# FPGA.net
KiCad netlist of a schematic drawn in Altium Designer
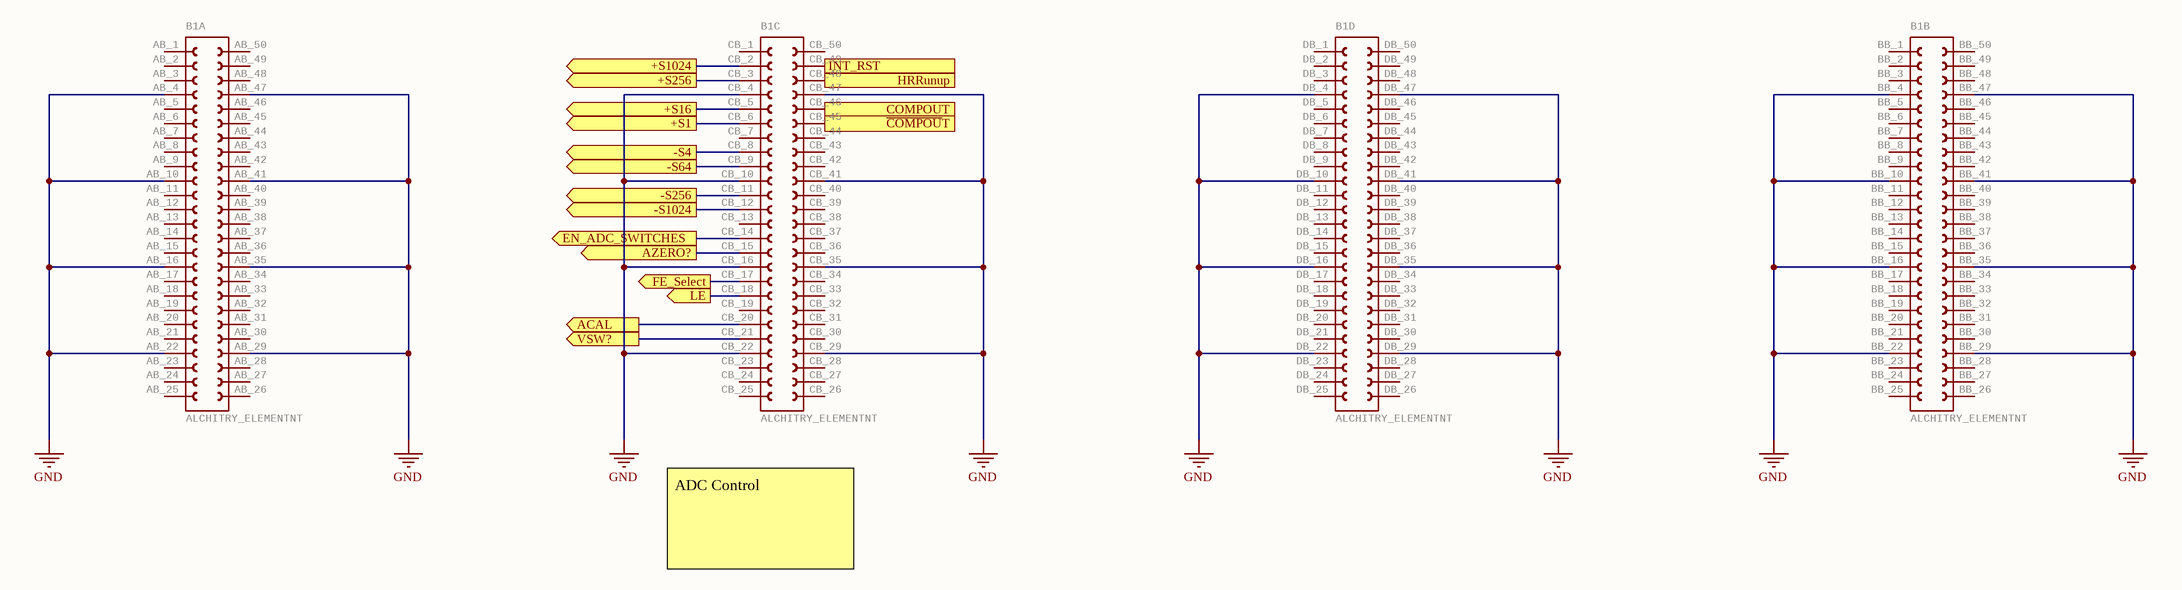
[diagram p0: FPGA.SchDoc]

(export (version "E")
  (design (tool "Eeschema 10.0.6"))
  (components
    (comp (ref "B1")
      (value "ALCHITRY_ELEMENTNT")
      (footprint "ELEMENT_NO_TOP")
      (libsource (lib "alchitry_elements.Library") (part "ALCHITRY_ELEMENTNT"))
    )
  )
  (nets
    (net (code "1") (name "/+S1") (class "Default")
      (node (ref "B1") (pin "CB_6") (pinfunction "6_CB_6") (pintype "passive"))
    )
    (net (code "2") (name "/+S16") (class "Default")
      (node (ref "B1") (pin "CB_5") (pinfunction "5_CB_5") (pintype "passive"))
    )
    (net (code "3") (name "/+S256") (class "Default")
      (node (ref "B1") (pin "CB_3") (pinfunction "3_CB_3") (pintype "passive"))
    )
    (net (code "4") (name "/+S1024") (class "Default")
      (node (ref "B1") (pin "CB_2") (pinfunction "2_CB_2") (pintype "passive"))
    )
    (net (code "5") (name "/-S4") (class "Default")
      (node (ref "B1") (pin "CB_8") (pinfunction "8_CB_8") (pintype "passive"))
    )
    (net (code "6") (name "/-S64") (class "Default")
      (node (ref "B1") (pin "CB_9") (pinfunction "9_CB_9") (pintype "passive"))
    )
    (net (code "7") (name "/-S256") (class "Default")
      (node (ref "B1") (pin "CB_11") (pinfunction "11_CB_11") (pintype "passive"))
    )
    (net (code "8") (name "/-S1024") (class "Default")
      (node (ref "B1") (pin "CB_12") (pinfunction "12_CB_12") (pintype "passive"))
    )
    (net (code "9") (name "/ACAL") (class "Default")
      (node (ref "B1") (pin "CB_20") (pinfunction "20_CB_20") (pintype "passive"))
    )
    (net (code "10") (name "/AZERO?") (class "Default")
      (node (ref "B1") (pin "CB_15") (pinfunction "15_CB_15") (pintype "passive"))
    )
    (net (code "11") (name "/COMPOUT") (class "Default")
      (node (ref "B1") (pin "CB_46") (pinfunction "46_CB_46") (pintype "passive"))
    )
    (net (code "12") (name "/EN_ADC_SWITCHES") (class "Default")
      (node (ref "B1") (pin "CB_14") (pinfunction "14_CB_14") (pintype "passive"))
    )
    (net (code "13") (name "/FE_Select") (class "Default")
      (node (ref "B1") (pin "CB_17") (pinfunction "17_CB_17") (pintype "passive"))
    )
    (net (code "14") (name "/HRRunup") (class "Default")
      (node (ref "B1") (pin "CB_48") (pinfunction "48_CB_48") (pintype "passive"))
    )
    (net (code "15") (name "/INT_RST") (class "Default")
      (node (ref "B1") (pin "CB_49") (pinfunction "49_CB_49") (pintype "passive"))
    )
    (net (code "16") (name "/LE") (class "Default")
      (node (ref "B1") (pin "CB_18") (pinfunction "18_CB_18") (pintype "passive"))
    )
    (net (code "17") (name "/VSW?") (class "Default")
      (node (ref "B1") (pin "CB_21") (pinfunction "21_CB_21") (pintype "passive"))
    )
    (net (code "18") (name "/~{COMPOU}T") (class "Default")
      (node (ref "B1") (pin "CB_45") (pinfunction "45_CB_45") (pintype "passive"))
    )
    (net (code "19") (name "GND") (class "Default")
      (node (ref "B1") (pin "AB_10") (pinfunction "10_AB_10") (pintype "passive"))
      (node (ref "B1") (pin "AB_16") (pinfunction "16_AB_16") (pintype "passive"))
      (node (ref "B1") (pin "AB_22") (pinfunction "22_AB_22") (pintype "passive"))
      (node (ref "B1") (pin "AB_29") (pinfunction "29_AB_29") (pintype "passive"))
      (node (ref "B1") (pin "AB_35") (pinfunction "35_AB_35") (pintype "passive"))
      (node (ref "B1") (pin "AB_4") (pinfunction "4_AB_4") (pintype "passive"))
      (node (ref "B1") (pin "AB_41") (pinfunction "41_AB_41") (pintype "passive"))
      (node (ref "B1") (pin "AB_47") (pinfunction "47_AB_47") (pintype "passive"))
      (node (ref "B1") (pin "BB_10") (pinfunction "10_BB_10") (pintype "passive"))
      (node (ref "B1") (pin "BB_16") (pinfunction "16_BB_16") (pintype "passive"))
      (node (ref "B1") (pin "BB_22") (pinfunction "22_BB_22") (pintype "passive"))
      (node (ref "B1") (pin "BB_29") (pinfunction "29_BB_29") (pintype "passive"))
      (node (ref "B1") (pin "BB_35") (pinfunction "35_BB_35") (pintype "passive"))
      (node (ref "B1") (pin "BB_4") (pinfunction "4_BB_4") (pintype "passive"))
      (node (ref "B1") (pin "BB_41") (pinfunction "41_BB_41") (pintype "passive"))
      (node (ref "B1") (pin "BB_47") (pinfunction "47_BB_47") (pintype "passive"))
      (node (ref "B1") (pin "CB_10") (pinfunction "10_CB_10") (pintype "passive"))
      (node (ref "B1") (pin "CB_16") (pinfunction "16_CB_16") (pintype "passive"))
      (node (ref "B1") (pin "CB_22") (pinfunction "22_CB_22") (pintype "passive"))
      (node (ref "B1") (pin "CB_29") (pinfunction "29_CB_29") (pintype "passive"))
      (node (ref "B1") (pin "CB_35") (pinfunction "35_CB_35") (pintype "passive"))
      (node (ref "B1") (pin "CB_4") (pinfunction "4_CB_4") (pintype "passive"))
      (node (ref "B1") (pin "CB_41") (pinfunction "41_CB_41") (pintype "passive"))
      (node (ref "B1") (pin "CB_47") (pinfunction "47_CB_47") (pintype "passive"))
      (node (ref "B1") (pin "DB_10") (pinfunction "10_DB_10") (pintype "passive"))
      (node (ref "B1") (pin "DB_16") (pinfunction "16_DB_16") (pintype "passive"))
      (node (ref "B1") (pin "DB_22") (pinfunction "22_DB_22") (pintype "passive"))
      (node (ref "B1") (pin "DB_29") (pinfunction "29_DB_29") (pintype "passive"))
      (node (ref "B1") (pin "DB_35") (pinfunction "35_DB_35") (pintype "passive"))
      (node (ref "B1") (pin "DB_4") (pinfunction "4_DB_4") (pintype "passive"))
      (node (ref "B1") (pin "DB_41") (pinfunction "41_DB_41") (pintype "passive"))
      (node (ref "B1") (pin "DB_47") (pinfunction "47_DB_47") (pintype "passive"))
    )
    (net (code "20") (name "unconnected-(B1A-1-PadAB_1)") (class "Default")
      (node (ref "B1") (pin "AB_1") (pinfunction "1_AB_1") (pintype "passive"))
    )
    (net (code "21") (name "unconnected-(B1A-2-PadAB_2)") (class "Default")
      (node (ref "B1") (pin "AB_2") (pinfunction "2_AB_2") (pintype "passive"))
    )
    (net (code "22") (name "unconnected-(B1A-3-PadAB_3)") (class "Default")
      (node (ref "B1") (pin "AB_3") (pinfunction "3_AB_3") (pintype "passive"))
    )
    (net (code "23") (name "unconnected-(B1A-5-PadAB_5)") (class "Default")
      (node (ref "B1") (pin "AB_5") (pinfunction "5_AB_5") (pintype "passive"))
    )
    (net (code "24") (name "unconnected-(B1A-6-PadAB_6)") (class "Default")
      (node (ref "B1") (pin "AB_6") (pinfunction "6_AB_6") (pintype "passive"))
    )
    (net (code "25") (name "unconnected-(B1A-7-PadAB_7)") (class "Default")
      (node (ref "B1") (pin "AB_7") (pinfunction "7_AB_7") (pintype "passive"))
    )
    (net (code "26") (name "unconnected-(B1A-8-PadAB_8)") (class "Default")
      (node (ref "B1") (pin "AB_8") (pinfunction "8_AB_8") (pintype "passive"))
    )
    (net (code "27") (name "unconnected-(B1A-9-PadAB_9)") (class "Default")
      (node (ref "B1") (pin "AB_9") (pinfunction "9_AB_9") (pintype "passive"))
    )
    (net (code "28") (name "unconnected-(B1A-11-PadAB_11)") (class "Default")
      (node (ref "B1") (pin "AB_11") (pinfunction "11_AB_11") (pintype "passive"))
    )
    (net (code "29") (name "unconnected-(B1A-12-PadAB_12)") (class "Default")
      (node (ref "B1") (pin "AB_12") (pinfunction "12_AB_12") (pintype "passive"))
    )
    (net (code "30") (name "unconnected-(B1A-13-PadAB_13)") (class "Default")
      (node (ref "B1") (pin "AB_13") (pinfunction "13_AB_13") (pintype "passive"))
    )
    (net (code "31") (name "unconnected-(B1A-14-PadAB_14)") (class "Default")
      (node (ref "B1") (pin "AB_14") (pinfunction "14_AB_14") (pintype "passive"))
    )
    (net (code "32") (name "unconnected-(B1A-15-PadAB_15)") (class "Default")
      (node (ref "B1") (pin "AB_15") (pinfunction "15_AB_15") (pintype "passive"))
    )
    (net (code "33") (name "unconnected-(B1A-17-PadAB_17)") (class "Default")
      (node (ref "B1") (pin "AB_17") (pinfunction "17_AB_17") (pintype "passive"))
    )
    (net (code "34") (name "unconnected-(B1A-18-PadAB_18)") (class "Default")
      (node (ref "B1") (pin "AB_18") (pinfunction "18_AB_18") (pintype "passive"))
    )
    (net (code "35") (name "unconnected-(B1A-19-PadAB_19)") (class "Default")
      (node (ref "B1") (pin "AB_19") (pinfunction "19_AB_19") (pintype "passive"))
    )
    (net (code "36") (name "unconnected-(B1A-20-PadAB_20)") (class "Default")
      (node (ref "B1") (pin "AB_20") (pinfunction "20_AB_20") (pintype "passive"))
    )
    (net (code "37") (name "unconnected-(B1A-21-PadAB_21)") (class "Default")
      (node (ref "B1") (pin "AB_21") (pinfunction "21_AB_21") (pintype "passive"))
    )
    (net (code "38") (name "unconnected-(B1A-23-PadAB_23)") (class "Default")
      (node (ref "B1") (pin "AB_23") (pinfunction "23_AB_23") (pintype "passive"))
    )
    (net (code "39") (name "unconnected-(B1A-24-PadAB_24)") (class "Default")
      (node (ref "B1") (pin "AB_24") (pinfunction "24_AB_24") (pintype "passive"))
    )
    (net (code "40") (name "unconnected-(B1A-25-PadAB_25)") (class "Default")
      (node (ref "B1") (pin "AB_25") (pinfunction "25_AB_25") (pintype "passive"))
    )
    (net (code "41") (name "unconnected-(B1A-26-PadAB_26)") (class "Default")
      (node (ref "B1") (pin "AB_26") (pinfunction "26_AB_26") (pintype "passive"))
    )
    (net (code "42") (name "unconnected-(B1A-27-PadAB_27)") (class "Default")
      (node (ref "B1") (pin "AB_27") (pinfunction "27_AB_27") (pintype "passive"))
    )
    (net (code "43") (name "unconnected-(B1A-28-PadAB_28)") (class "Default")
      (node (ref "B1") (pin "AB_28") (pinfunction "28_AB_28") (pintype "passive"))
    )
    (net (code "44") (name "unconnected-(B1A-30-PadAB_30)") (class "Default")
      (node (ref "B1") (pin "AB_30") (pinfunction "30_AB_30") (pintype "passive"))
    )
    (net (code "45") (name "unconnected-(B1A-31-PadAB_31)") (class "Default")
      (node (ref "B1") (pin "AB_31") (pinfunction "31_AB_31") (pintype "passive"))
    )
    (net (code "46") (name "unconnected-(B1A-32-PadAB_32)") (class "Default")
      (node (ref "B1") (pin "AB_32") (pinfunction "32_AB_32") (pintype "passive"))
    )
    (net (code "47") (name "unconnected-(B1A-33-PadAB_33)") (class "Default")
      (node (ref "B1") (pin "AB_33") (pinfunction "33_AB_33") (pintype "passive"))
    )
    (net (code "48") (name "unconnected-(B1A-34-PadAB_34)") (class "Default")
      (node (ref "B1") (pin "AB_34") (pinfunction "34_AB_34") (pintype "passive"))
    )
    (net (code "49") (name "unconnected-(B1A-36-PadAB_36)") (class "Default")
      (node (ref "B1") (pin "AB_36") (pinfunction "36_AB_36") (pintype "passive"))
    )
    (net (code "50") (name "unconnected-(B1A-37-PadAB_37)") (class "Default")
      (node (ref "B1") (pin "AB_37") (pinfunction "37_AB_37") (pintype "passive"))
    )
    (net (code "51") (name "unconnected-(B1A-38-PadAB_38)") (class "Default")
      (node (ref "B1") (pin "AB_38") (pinfunction "38_AB_38") (pintype "passive"))
    )
    (net (code "52") (name "unconnected-(B1A-39-PadAB_39)") (class "Default")
      (node (ref "B1") (pin "AB_39") (pinfunction "39_AB_39") (pintype "passive"))
    )
    (net (code "53") (name "unconnected-(B1A-40-PadAB_40)") (class "Default")
      (node (ref "B1") (pin "AB_40") (pinfunction "40_AB_40") (pintype "passive"))
    )
    (net (code "54") (name "unconnected-(B1A-42-PadAB_42)") (class "Default")
      (node (ref "B1") (pin "AB_42") (pinfunction "42_AB_42") (pintype "passive"))
    )
    (net (code "55") (name "unconnected-(B1A-43-PadAB_43)") (class "Default")
      (node (ref "B1") (pin "AB_43") (pinfunction "43_AB_43") (pintype "passive"))
    )
    (net (code "56") (name "unconnected-(B1A-44-PadAB_44)") (class "Default")
      (node (ref "B1") (pin "AB_44") (pinfunction "44_AB_44") (pintype "passive"))
    )
    (net (code "57") (name "unconnected-(B1A-45-PadAB_45)") (class "Default")
      (node (ref "B1") (pin "AB_45") (pinfunction "45_AB_45") (pintype "passive"))
    )
    (net (code "58") (name "unconnected-(B1A-46-PadAB_46)") (class "Default")
      (node (ref "B1") (pin "AB_46") (pinfunction "46_AB_46") (pintype "passive"))
    )
    (net (code "59") (name "unconnected-(B1A-48-PadAB_48)") (class "Default")
      (node (ref "B1") (pin "AB_48") (pinfunction "48_AB_48") (pintype "passive"))
    )
    (net (code "60") (name "unconnected-(B1A-49-PadAB_49)") (class "Default")
      (node (ref "B1") (pin "AB_49") (pinfunction "49_AB_49") (pintype "passive"))
    )
    (net (code "61") (name "unconnected-(B1A-50-PadAB_50)") (class "Default")
      (node (ref "B1") (pin "AB_50") (pinfunction "50_AB_50") (pintype "passive"))
    )
    (net (code "62") (name "unconnected-(B1B-1-PadBB_1)") (class "Default")
      (node (ref "B1") (pin "BB_1") (pinfunction "1_BB_1") (pintype "passive"))
    )
    (net (code "63") (name "unconnected-(B1B-2-PadBB_2)") (class "Default")
      (node (ref "B1") (pin "BB_2") (pinfunction "2_BB_2") (pintype "passive"))
    )
    (net (code "64") (name "unconnected-(B1B-3-PadBB_3)") (class "Default")
      (node (ref "B1") (pin "BB_3") (pinfunction "3_BB_3") (pintype "passive"))
    )
    (net (code "65") (name "unconnected-(B1B-5-PadBB_5)") (class "Default")
      (node (ref "B1") (pin "BB_5") (pinfunction "5_BB_5") (pintype "passive"))
    )
    (net (code "66") (name "unconnected-(B1B-6-PadBB_6)") (class "Default")
      (node (ref "B1") (pin "BB_6") (pinfunction "6_BB_6") (pintype "passive"))
    )
    (net (code "67") (name "unconnected-(B1B-7-PadBB_7)") (class "Default")
      (node (ref "B1") (pin "BB_7") (pinfunction "7_BB_7") (pintype "passive"))
    )
    (net (code "68") (name "unconnected-(B1B-8-PadBB_8)") (class "Default")
      (node (ref "B1") (pin "BB_8") (pinfunction "8_BB_8") (pintype "passive"))
    )
    (net (code "69") (name "unconnected-(B1B-9-PadBB_9)") (class "Default")
      (node (ref "B1") (pin "BB_9") (pinfunction "9_BB_9") (pintype "passive"))
    )
    (net (code "70") (name "unconnected-(B1B-11-PadBB_11)") (class "Default")
      (node (ref "B1") (pin "BB_11") (pinfunction "11_BB_11") (pintype "passive"))
    )
    (net (code "71") (name "unconnected-(B1B-12-PadBB_12)") (class "Default")
      (node (ref "B1") (pin "BB_12") (pinfunction "12_BB_12") (pintype "passive"))
    )
    (net (code "72") (name "unconnected-(B1B-13-PadBB_13)") (class "Default")
      (node (ref "B1") (pin "BB_13") (pinfunction "13_BB_13") (pintype "passive"))
    )
    (net (code "73") (name "unconnected-(B1B-14-PadBB_14)") (class "Default")
      (node (ref "B1") (pin "BB_14") (pinfunction "14_BB_14") (pintype "passive"))
    )
    (net (code "74") (name "unconnected-(B1B-15-PadBB_15)") (class "Default")
      (node (ref "B1") (pin "BB_15") (pinfunction "15_BB_15") (pintype "passive"))
    )
    (net (code "75") (name "unconnected-(B1B-17-PadBB_17)") (class "Default")
      (node (ref "B1") (pin "BB_17") (pinfunction "17_BB_17") (pintype "passive"))
    )
    (net (code "76") (name "unconnected-(B1B-18-PadBB_18)") (class "Default")
      (node (ref "B1") (pin "BB_18") (pinfunction "18_BB_18") (pintype "passive"))
    )
    (net (code "77") (name "unconnected-(B1B-19-PadBB_19)") (class "Default")
      (node (ref "B1") (pin "BB_19") (pinfunction "19_BB_19") (pintype "passive"))
    )
    (net (code "78") (name "unconnected-(B1B-20-PadBB_20)") (class "Default")
      (node (ref "B1") (pin "BB_20") (pinfunction "20_BB_20") (pintype "passive"))
    )
    (net (code "79") (name "unconnected-(B1B-21-PadBB_21)") (class "Default")
      (node (ref "B1") (pin "BB_21") (pinfunction "21_BB_21") (pintype "passive"))
    )
    (net (code "80") (name "unconnected-(B1B-23-PadBB_23)") (class "Default")
      (node (ref "B1") (pin "BB_23") (pinfunction "23_BB_23") (pintype "passive"))
    )
    (net (code "81") (name "unconnected-(B1B-24-PadBB_24)") (class "Default")
      (node (ref "B1") (pin "BB_24") (pinfunction "24_BB_24") (pintype "passive"))
    )
    (net (code "82") (name "unconnected-(B1B-25-PadBB_25)") (class "Default")
      (node (ref "B1") (pin "BB_25") (pinfunction "25_BB_25") (pintype "passive"))
    )
    (net (code "83") (name "unconnected-(B1B-26-PadBB_26)") (class "Default")
      (node (ref "B1") (pin "BB_26") (pinfunction "26_BB_26") (pintype "passive"))
    )
    (net (code "84") (name "unconnected-(B1B-27-PadBB_27)") (class "Default")
      (node (ref "B1") (pin "BB_27") (pinfunction "27_BB_27") (pintype "passive"))
    )
    (net (code "85") (name "unconnected-(B1B-28-PadBB_28)") (class "Default")
      (node (ref "B1") (pin "BB_28") (pinfunction "28_BB_28") (pintype "passive"))
    )
    (net (code "86") (name "unconnected-(B1B-30-PadBB_30)") (class "Default")
      (node (ref "B1") (pin "BB_30") (pinfunction "30_BB_30") (pintype "passive"))
    )
    (net (code "87") (name "unconnected-(B1B-31-PadBB_31)") (class "Default")
      (node (ref "B1") (pin "BB_31") (pinfunction "31_BB_31") (pintype "passive"))
    )
    (net (code "88") (name "unconnected-(B1B-32-PadBB_32)") (class "Default")
      (node (ref "B1") (pin "BB_32") (pinfunction "32_BB_32") (pintype "passive"))
    )
    (net (code "89") (name "unconnected-(B1B-33-PadBB_33)") (class "Default")
      (node (ref "B1") (pin "BB_33") (pinfunction "33_BB_33") (pintype "passive"))
    )
    (net (code "90") (name "unconnected-(B1B-34-PadBB_34)") (class "Default")
      (node (ref "B1") (pin "BB_34") (pinfunction "34_BB_34") (pintype "passive"))
    )
    (net (code "91") (name "unconnected-(B1B-36-PadBB_36)") (class "Default")
      (node (ref "B1") (pin "BB_36") (pinfunction "36_BB_36") (pintype "passive"))
    )
    (net (code "92") (name "unconnected-(B1B-37-PadBB_37)") (class "Default")
      (node (ref "B1") (pin "BB_37") (pinfunction "37_BB_37") (pintype "passive"))
    )
    (net (code "93") (name "unconnected-(B1B-38-PadBB_38)") (class "Default")
      (node (ref "B1") (pin "BB_38") (pinfunction "38_BB_38") (pintype "passive"))
    )
    (net (code "94") (name "unconnected-(B1B-39-PadBB_39)") (class "Default")
      (node (ref "B1") (pin "BB_39") (pinfunction "39_BB_39") (pintype "passive"))
    )
    (net (code "95") (name "unconnected-(B1B-40-PadBB_40)") (class "Default")
      (node (ref "B1") (pin "BB_40") (pinfunction "40_BB_40") (pintype "passive"))
    )
    (net (code "96") (name "unconnected-(B1B-42-PadBB_42)") (class "Default")
      (node (ref "B1") (pin "BB_42") (pinfunction "42_BB_42") (pintype "passive"))
    )
    (net (code "97") (name "unconnected-(B1B-43-PadBB_43)") (class "Default")
      (node (ref "B1") (pin "BB_43") (pinfunction "43_BB_43") (pintype "passive"))
    )
    (net (code "98") (name "unconnected-(B1B-44-PadBB_44)") (class "Default")
      (node (ref "B1") (pin "BB_44") (pinfunction "44_BB_44") (pintype "passive"))
    )
    (net (code "99") (name "unconnected-(B1B-45-PadBB_45)") (class "Default")
      (node (ref "B1") (pin "BB_45") (pinfunction "45_BB_45") (pintype "passive"))
    )
    (net (code "100") (name "unconnected-(B1B-46-PadBB_46)") (class "Default")
      (node (ref "B1") (pin "BB_46") (pinfunction "46_BB_46") (pintype "passive"))
    )
    (net (code "101") (name "unconnected-(B1B-48-PadBB_48)") (class "Default")
      (node (ref "B1") (pin "BB_48") (pinfunction "48_BB_48") (pintype "passive"))
    )
    (net (code "102") (name "unconnected-(B1B-49-PadBB_49)") (class "Default")
      (node (ref "B1") (pin "BB_49") (pinfunction "49_BB_49") (pintype "passive"))
    )
    (net (code "103") (name "unconnected-(B1B-50-PadBB_50)") (class "Default")
      (node (ref "B1") (pin "BB_50") (pinfunction "50_BB_50") (pintype "passive"))
    )
    (net (code "104") (name "unconnected-(B1C-1-PadCB_1)") (class "Default")
      (node (ref "B1") (pin "CB_1") (pinfunction "1_CB_1") (pintype "passive"))
    )
    (net (code "105") (name "unconnected-(B1C-7-PadCB_7)") (class "Default")
      (node (ref "B1") (pin "CB_7") (pinfunction "7_CB_7") (pintype "passive"))
    )
    (net (code "106") (name "unconnected-(B1C-13-PadCB_13)") (class "Default")
      (node (ref "B1") (pin "CB_13") (pinfunction "13_CB_13") (pintype "passive"))
    )
    (net (code "107") (name "unconnected-(B1C-19-PadCB_19)") (class "Default")
      (node (ref "B1") (pin "CB_19") (pinfunction "19_CB_19") (pintype "passive"))
    )
    (net (code "108") (name "unconnected-(B1C-23-PadCB_23)") (class "Default")
      (node (ref "B1") (pin "CB_23") (pinfunction "23_CB_23") (pintype "passive"))
    )
    (net (code "109") (name "unconnected-(B1C-24-PadCB_24)") (class "Default")
      (node (ref "B1") (pin "CB_24") (pinfunction "24_CB_24") (pintype "passive"))
    )
    (net (code "110") (name "unconnected-(B1C-25-PadCB_25)") (class "Default")
      (node (ref "B1") (pin "CB_25") (pinfunction "25_CB_25") (pintype "passive"))
    )
    (net (code "111") (name "unconnected-(B1C-26-PadCB_26)") (class "Default")
      (node (ref "B1") (pin "CB_26") (pinfunction "26_CB_26") (pintype "passive"))
    )
    (net (code "112") (name "unconnected-(B1C-27-PadCB_27)") (class "Default")
      (node (ref "B1") (pin "CB_27") (pinfunction "27_CB_27") (pintype "passive"))
    )
    (net (code "113") (name "unconnected-(B1C-28-PadCB_28)") (class "Default")
      (node (ref "B1") (pin "CB_28") (pinfunction "28_CB_28") (pintype "passive"))
    )
    (net (code "114") (name "unconnected-(B1C-30-PadCB_30)") (class "Default")
      (node (ref "B1") (pin "CB_30") (pinfunction "30_CB_30") (pintype "passive"))
    )
    (net (code "115") (name "unconnected-(B1C-31-PadCB_31)") (class "Default")
      (node (ref "B1") (pin "CB_31") (pinfunction "31_CB_31") (pintype "passive"))
    )
    (net (code "116") (name "unconnected-(B1C-32-PadCB_32)") (class "Default")
      (node (ref "B1") (pin "CB_32") (pinfunction "32_CB_32") (pintype "passive"))
    )
    (net (code "117") (name "unconnected-(B1C-33-PadCB_33)") (class "Default")
      (node (ref "B1") (pin "CB_33") (pinfunction "33_CB_33") (pintype "passive"))
    )
    (net (code "118") (name "unconnected-(B1C-34-PadCB_34)") (class "Default")
      (node (ref "B1") (pin "CB_34") (pinfunction "34_CB_34") (pintype "passive"))
    )
    (net (code "119") (name "unconnected-(B1C-36-PadCB_36)") (class "Default")
      (node (ref "B1") (pin "CB_36") (pinfunction "36_CB_36") (pintype "passive"))
    )
    (net (code "120") (name "unconnected-(B1C-37-PadCB_37)") (class "Default")
      (node (ref "B1") (pin "CB_37") (pinfunction "37_CB_37") (pintype "passive"))
    )
    (net (code "121") (name "unconnected-(B1C-38-PadCB_38)") (class "Default")
      (node (ref "B1") (pin "CB_38") (pinfunction "38_CB_38") (pintype "passive"))
    )
    (net (code "122") (name "unconnected-(B1C-39-PadCB_39)") (class "Default")
      (node (ref "B1") (pin "CB_39") (pinfunction "39_CB_39") (pintype "passive"))
    )
    (net (code "123") (name "unconnected-(B1C-40-PadCB_40)") (class "Default")
      (node (ref "B1") (pin "CB_40") (pinfunction "40_CB_40") (pintype "passive"))
    )
    (net (code "124") (name "unconnected-(B1C-42-PadCB_42)") (class "Default")
      (node (ref "B1") (pin "CB_42") (pinfunction "42_CB_42") (pintype "passive"))
    )
    (net (code "125") (name "unconnected-(B1C-43-PadCB_43)") (class "Default")
      (node (ref "B1") (pin "CB_43") (pinfunction "43_CB_43") (pintype "passive"))
    )
    (net (code "126") (name "unconnected-(B1C-44-PadCB_44)") (class "Default")
      (node (ref "B1") (pin "CB_44") (pinfunction "44_CB_44") (pintype "passive"))
    )
    (net (code "127") (name "unconnected-(B1C-50-PadCB_50)") (class "Default")
      (node (ref "B1") (pin "CB_50") (pinfunction "50_CB_50") (pintype "passive"))
    )
    (net (code "128") (name "unconnected-(B1D-1-PadDB_1)") (class "Default")
      (node (ref "B1") (pin "DB_1") (pinfunction "1_DB_1") (pintype "passive"))
    )
    (net (code "129") (name "unconnected-(B1D-2-PadDB_2)") (class "Default")
      (node (ref "B1") (pin "DB_2") (pinfunction "2_DB_2") (pintype "passive"))
    )
    (net (code "130") (name "unconnected-(B1D-3-PadDB_3)") (class "Default")
      (node (ref "B1") (pin "DB_3") (pinfunction "3_DB_3") (pintype "passive"))
    )
    (net (code "131") (name "unconnected-(B1D-5-PadDB_5)") (class "Default")
      (node (ref "B1") (pin "DB_5") (pinfunction "5_DB_5") (pintype "passive"))
    )
    (net (code "132") (name "unconnected-(B1D-6-PadDB_6)") (class "Default")
      (node (ref "B1") (pin "DB_6") (pinfunction "6_DB_6") (pintype "passive"))
    )
    (net (code "133") (name "unconnected-(B1D-7-PadDB_7)") (class "Default")
      (node (ref "B1") (pin "DB_7") (pinfunction "7_DB_7") (pintype "passive"))
    )
    (net (code "134") (name "unconnected-(B1D-8-PadDB_8)") (class "Default")
      (node (ref "B1") (pin "DB_8") (pinfunction "8_DB_8") (pintype "passive"))
    )
    (net (code "135") (name "unconnected-(B1D-9-PadDB_9)") (class "Default")
      (node (ref "B1") (pin "DB_9") (pinfunction "9_DB_9") (pintype "passive"))
    )
    (net (code "136") (name "unconnected-(B1D-11-PadDB_11)") (class "Default")
      (node (ref "B1") (pin "DB_11") (pinfunction "11_DB_11") (pintype "passive"))
    )
    (net (code "137") (name "unconnected-(B1D-12-PadDB_12)") (class "Default")
      (node (ref "B1") (pin "DB_12") (pinfunction "12_DB_12") (pintype "passive"))
    )
    (net (code "138") (name "unconnected-(B1D-13-PadDB_13)") (class "Default")
      (node (ref "B1") (pin "DB_13") (pinfunction "13_DB_13") (pintype "passive"))
    )
    (net (code "139") (name "unconnected-(B1D-14-PadDB_14)") (class "Default")
      (node (ref "B1") (pin "DB_14") (pinfunction "14_DB_14") (pintype "passive"))
    )
    (net (code "140") (name "unconnected-(B1D-15-PadDB_15)") (class "Default")
      (node (ref "B1") (pin "DB_15") (pinfunction "15_DB_15") (pintype "passive"))
    )
    (net (code "141") (name "unconnected-(B1D-17-PadDB_17)") (class "Default")
      (node (ref "B1") (pin "DB_17") (pinfunction "17_DB_17") (pintype "passive"))
    )
    (net (code "142") (name "unconnected-(B1D-18-PadDB_18)") (class "Default")
      (node (ref "B1") (pin "DB_18") (pinfunction "18_DB_18") (pintype "passive"))
    )
    (net (code "143") (name "unconnected-(B1D-19-PadDB_19)") (class "Default")
      (node (ref "B1") (pin "DB_19") (pinfunction "19_DB_19") (pintype "passive"))
    )
    (net (code "144") (name "unconnected-(B1D-20-PadDB_20)") (class "Default")
      (node (ref "B1") (pin "DB_20") (pinfunction "20_DB_20") (pintype "passive"))
    )
    (net (code "145") (name "unconnected-(B1D-21-PadDB_21)") (class "Default")
      (node (ref "B1") (pin "DB_21") (pinfunction "21_DB_21") (pintype "passive"))
    )
    (net (code "146") (name "unconnected-(B1D-23-PadDB_23)") (class "Default")
      (node (ref "B1") (pin "DB_23") (pinfunction "23_DB_23") (pintype "passive"))
    )
    (net (code "147") (name "unconnected-(B1D-24-PadDB_24)") (class "Default")
      (node (ref "B1") (pin "DB_24") (pinfunction "24_DB_24") (pintype "passive"))
    )
    (net (code "148") (name "unconnected-(B1D-25-PadDB_25)") (class "Default")
      (node (ref "B1") (pin "DB_25") (pinfunction "25_DB_25") (pintype "passive"))
    )
    (net (code "149") (name "unconnected-(B1D-26-PadDB_26)") (class "Default")
      (node (ref "B1") (pin "DB_26") (pinfunction "26_DB_26") (pintype "passive"))
    )
    (net (code "150") (name "unconnected-(B1D-27-PadDB_27)") (class "Default")
      (node (ref "B1") (pin "DB_27") (pinfunction "27_DB_27") (pintype "passive"))
    )
    (net (code "151") (name "unconnected-(B1D-28-PadDB_28)") (class "Default")
      (node (ref "B1") (pin "DB_28") (pinfunction "28_DB_28") (pintype "passive"))
    )
    (net (code "152") (name "unconnected-(B1D-30-PadDB_30)") (class "Default")
      (node (ref "B1") (pin "DB_30") (pinfunction "30_DB_30") (pintype "passive"))
    )
    (net (code "153") (name "unconnected-(B1D-31-PadDB_31)") (class "Default")
      (node (ref "B1") (pin "DB_31") (pinfunction "31_DB_31") (pintype "passive"))
    )
    (net (code "154") (name "unconnected-(B1D-32-PadDB_32)") (class "Default")
      (node (ref "B1") (pin "DB_32") (pinfunction "32_DB_32") (pintype "passive"))
    )
    (net (code "155") (name "unconnected-(B1D-33-PadDB_33)") (class "Default")
      (node (ref "B1") (pin "DB_33") (pinfunction "33_DB_33") (pintype "passive"))
    )
    (net (code "156") (name "unconnected-(B1D-34-PadDB_34)") (class "Default")
      (node (ref "B1") (pin "DB_34") (pinfunction "34_DB_34") (pintype "passive"))
    )
    (net (code "157") (name "unconnected-(B1D-36-PadDB_36)") (class "Default")
      (node (ref "B1") (pin "DB_36") (pinfunction "36_DB_36") (pintype "passive"))
    )
    (net (code "158") (name "unconnected-(B1D-37-PadDB_37)") (class "Default")
      (node (ref "B1") (pin "DB_37") (pinfunction "37_DB_37") (pintype "passive"))
    )
    (net (code "159") (name "unconnected-(B1D-38-PadDB_38)") (class "Default")
      (node (ref "B1") (pin "DB_38") (pinfunction "38_DB_38") (pintype "passive"))
    )
    (net (code "160") (name "unconnected-(B1D-39-PadDB_39)") (class "Default")
      (node (ref "B1") (pin "DB_39") (pinfunction "39_DB_39") (pintype "passive"))
    )
    (net (code "161") (name "unconnected-(B1D-40-PadDB_40)") (class "Default")
      (node (ref "B1") (pin "DB_40") (pinfunction "40_DB_40") (pintype "passive"))
    )
    (net (code "162") (name "unconnected-(B1D-42-PadDB_42)") (class "Default")
      (node (ref "B1") (pin "DB_42") (pinfunction "42_DB_42") (pintype "passive"))
    )
    (net (code "163") (name "unconnected-(B1D-43-PadDB_43)") (class "Default")
      (node (ref "B1") (pin "DB_43") (pinfunction "43_DB_43") (pintype "passive"))
    )
    (net (code "164") (name "unconnected-(B1D-44-PadDB_44)") (class "Default")
      (node (ref "B1") (pin "DB_44") (pinfunction "44_DB_44") (pintype "passive"))
    )
    (net (code "165") (name "unconnected-(B1D-45-PadDB_45)") (class "Default")
      (node (ref "B1") (pin "DB_45") (pinfunction "45_DB_45") (pintype "passive"))
    )
    (net (code "166") (name "unconnected-(B1D-46-PadDB_46)") (class "Default")
      (node (ref "B1") (pin "DB_46") (pinfunction "46_DB_46") (pintype "passive"))
    )
    (net (code "167") (name "unconnected-(B1D-48-PadDB_48)") (class "Default")
      (node (ref "B1") (pin "DB_48") (pinfunction "48_DB_48") (pintype "passive"))
    )
    (net (code "168") (name "unconnected-(B1D-49-PadDB_49)") (class "Default")
      (node (ref "B1") (pin "DB_49") (pinfunction "49_DB_49") (pintype "passive"))
    )
    (net (code "169") (name "unconnected-(B1D-50-PadDB_50)") (class "Default")
      (node (ref "B1") (pin "DB_50") (pinfunction "50_DB_50") (pintype "passive"))
    )
  )
)
